# Sheet1.net
KiCad netlist of a schematic drawn in Altium Designer
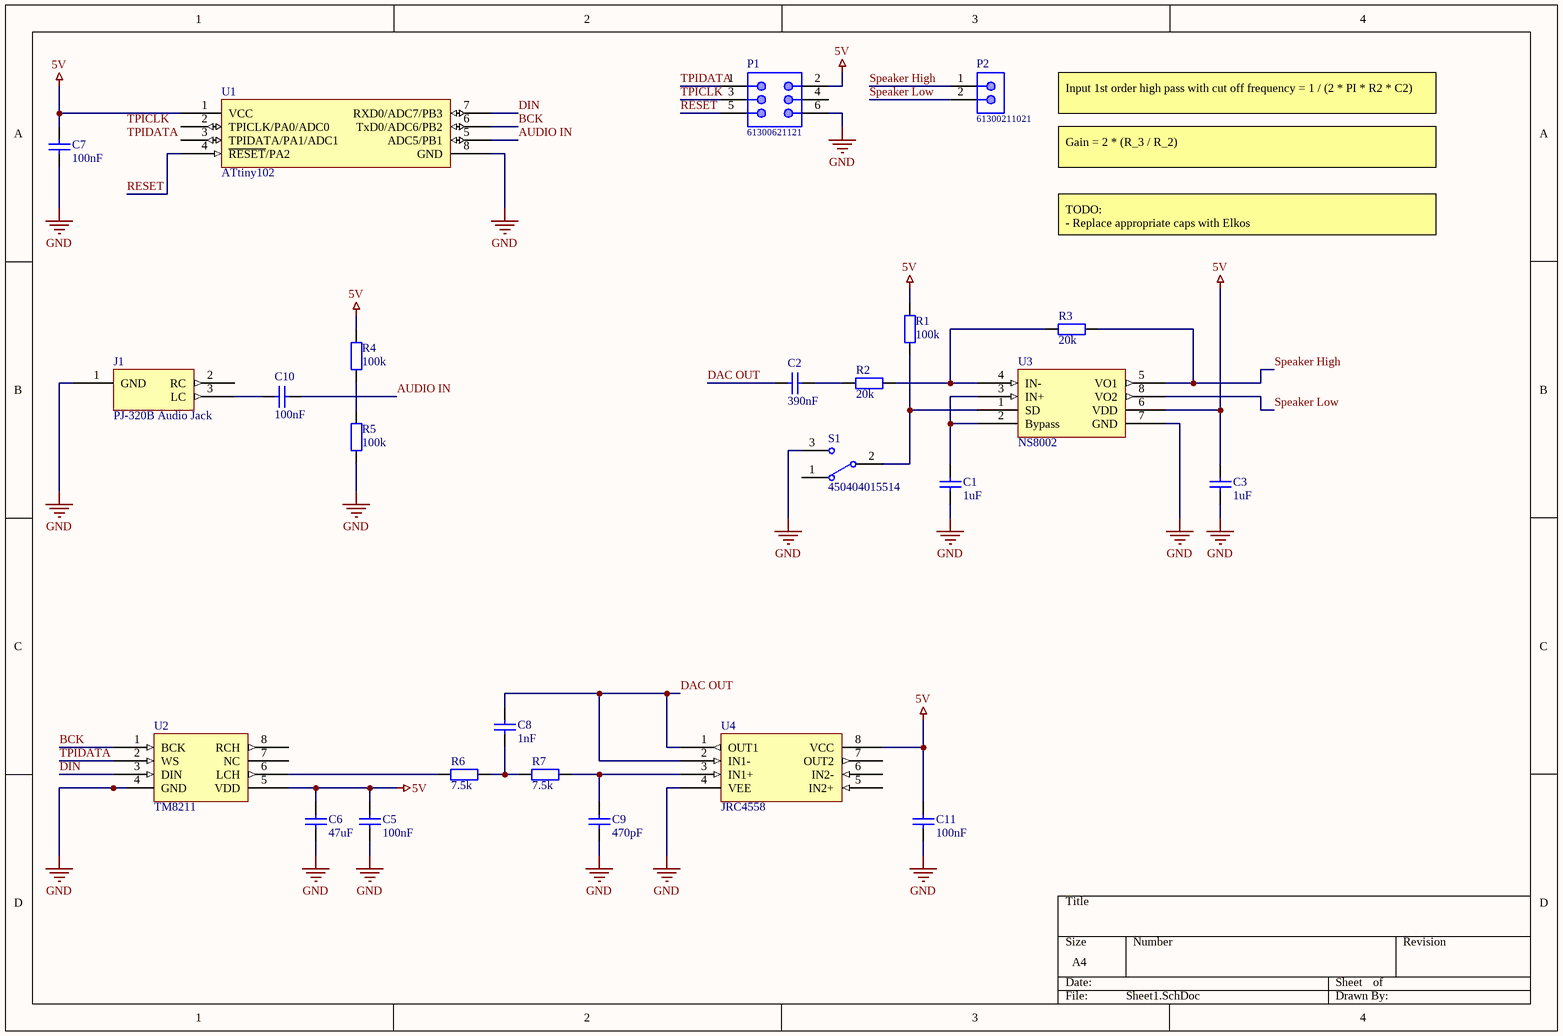
[diagram p0: Sheet1.SchDoc]

(export (version "E")
  (design (tool "Eeschema 10.0.6"))
  (components
    (comp (ref "C1")
      (value "1uF")
      (footprint "WCAP-CSGP_0805_H=1.25mm")
      (description "WCAP-CSGP General Purpose Ceramic Capacitors, size 0805, 1uF, +/-10%, 10VDC")
      (fields (field (name "PART NUMBER") "885012207022") (field (name "PUBLISHER") "Wurth Elektronik"))
      (libsource (lib "Altium_WCAP-CSGP (rev19a)") (part "885012207022"))
    )
    (comp (ref "C2")
      (value "390nF")
      (footprint "WCAP-CSGP_0402")
      (description "WCAP-CSGP General Purpose Ceramic Capacitors, size 0402, 1nF, +/-10%, 16VDC")
      (fields (field (name "PART NUMBER") "885012205025") (field (name "PUBLISHER") "Wurth Elektronik"))
      (libsource (lib "Altium_WCAP-CSGP (rev19a)") (part "885012205025"))
    )
    (comp (ref "C3")
      (value "1uF")
      (footprint "WCAP-CSGP_0805_H=1.25mm")
      (description "WCAP-CSGP General Purpose Ceramic Capacitors, size 0805, 1uF, +/-10%, 10VDC")
      (fields (field (name "PART NUMBER") "885012207022") (field (name "PUBLISHER") "Wurth Elektronik"))
      (libsource (lib "Altium_WCAP-CSGP (rev19a)") (part "885012207022"))
    )
    (comp (ref "C5")
      (value "100nF")
      (footprint "WCAP-CSGP_0805_H=1.25mm")
      (description "WCAP-CSGP General Purpose Ceramic Capacitors, size 0805, 1uF, +/-10%, 10VDC")
      (fields (field (name "PART NUMBER") "885012207022") (field (name "PUBLISHER") "Wurth Elektronik"))
      (libsource (lib "Altium_WCAP-CSGP (rev19a)") (part "885012207022"))
    )
    (comp (ref "C6")
      (value "47uF")
      (footprint "WCAP-CSGP_0805_H=1.25mm")
      (description "WCAP-CSGP General Purpose Ceramic Capacitors, size 0805, 1uF, +/-10%, 10VDC")
      (fields (field (name "PART NUMBER") "885012207022") (field (name "PUBLISHER") "Wurth Elektronik"))
      (libsource (lib "Altium_WCAP-CSGP (rev19a)") (part "885012207022"))
    )
    (comp (ref "C7")
      (value "100nF")
      (footprint "WCAP-CSGP_0805_H=1.25mm")
      (description "WCAP-CSGP General Purpose Ceramic Capacitors, size 0805, 1uF, +/-10%, 10VDC")
      (fields (field (name "PART NUMBER") "885012207022") (field (name "PUBLISHER") "Wurth Elektronik"))
      (libsource (lib "Altium_WCAP-CSGP (rev19a)") (part "885012207022"))
    )
    (comp (ref "C8")
      (value "1nF")
      (footprint "WCAP-CSGP_0402")
      (description "WCAP-CSGP General Purpose Ceramic Capacitors, size 0402, 1nF, +/-10%, 16VDC")
      (fields (field (name "PART NUMBER") "885012205025") (field (name "PUBLISHER") "Wurth Elektronik"))
      (libsource (lib "Altium_WCAP-CSGP (rev19a)") (part "885012205025"))
    )
    (comp (ref "C9")
      (value "470pF")
      (footprint "WCAP-CSGP_0402")
      (description "WCAP-CSGP General Purpose Ceramic Capacitors, size 0402, 1nF, +/-10%, 16VDC")
      (fields (field (name "PART NUMBER") "885012205025") (field (name "PUBLISHER") "Wurth Elektronik"))
      (libsource (lib "Altium_WCAP-CSGP (rev19a)") (part "885012205025"))
    )
    (comp (ref "C10")
      (value "100nF")
      (footprint "WCAP-CSGP_0805_H=1.25mm")
      (description "WCAP-CSGP General Purpose Ceramic Capacitors, size 0805, 1uF, +/-10%, 10VDC")
      (fields (field (name "PART NUMBER") "885012207022") (field (name "PUBLISHER") "Wurth Elektronik"))
      (libsource (lib "Altium_WCAP-CSGP (rev19a)") (part "885012207022"))
    )
    (comp (ref "C11")
      (value "100nF")
      (footprint "WCAP-CSGP_0805_H=1.25mm")
      (description "WCAP-CSGP General Purpose Ceramic Capacitors, size 0805, 1uF, +/-10%, 10VDC")
      (fields (field (name "PART NUMBER") "885012207022") (field (name "PUBLISHER") "Wurth Elektronik"))
      (libsource (lib "Altium_WCAP-CSGP (rev19a)") (part "885012207022"))
    )
    (comp (ref "J1")
      (value "PJ-320B Audio Jack")
      (footprint "PJ-320B Audio Jack")
      (libsource (lib "PJ-320B_AudioJack") (part "PJ-320B Audio Jack"))
    )
    (comp (ref "P1")
      (value "61300621121")
      (footprint "61300621121")
      (description "WR-PHD Pin Header, THT, pitch 2.54mm, Dual Row, Vertical, 6p")
      (fields (field (name "MANUFACTURER") "Wurth Elektronik"))
      (libsource (lib "61300311021_Altium_WR-PHD_rev20a") (part "61300621121"))
    )
    (comp (ref "P2")
      (value "61300211021")
      (footprint "61300211021")
      (description "WR-PHD Pin Header, THT, pitch 2.54mm, Single Row, Angled, 2p")
      (fields (field (name "MANUFACTURER") "Wurth Elektronik"))
      (libsource (lib "61300311021_Altium_WR-PHD_rev20a") (part "61300211021"))
    )
    (comp (ref "R1")
      (value "100k")
      (footprint "WRIS-PSMB_0805_H=0.22mm")
      (description "WRIS-PSMB Metal Plate Resistors, size 0805, 10mOhm, +/-1%, 0.5W")
      (fields (field (name "PART NUMBER") "580060720008") (field (name "PUBLISHER") "Wurth Elektronik"))
      (libsource (lib "") (part "580060720008_2"))
    )
    (comp (ref "R2")
      (value "20k")
      (footprint "WRIS-PSMB_0805_H=0.22mm")
      (description "WRIS-PSMB Metal Plate Resistors, size 0805, 10mOhm, +/-1%, 0.5W")
      (fields (field (name "PART NUMBER") "580060720008") (field (name "PUBLISHER") "Wurth Elektronik"))
      (libsource (lib "Altium_WRIS-PSMB (rev19a)") (part "580060720008"))
    )
    (comp (ref "R3")
      (value "20k")
      (footprint "WRIS-PSMB_0805_H=0.22mm")
      (description "WRIS-PSMB Metal Plate Resistors, size 0805, 10mOhm, +/-1%, 0.5W")
      (fields (field (name "PART NUMBER") "580060720008") (field (name "PUBLISHER") "Wurth Elektronik"))
      (libsource (lib "Altium_WRIS-PSMB (rev19a)") (part "580060720008"))
    )
    (comp (ref "R4")
      (value "100k")
      (footprint "WRIS-PSMB_0805_H=0.22mm")
      (description "WRIS-PSMB Metal Plate Resistors, size 0805, 10mOhm, +/-1%, 0.5W")
      (fields (field (name "PART NUMBER") "580060720008") (field (name "PUBLISHER") "Wurth Elektronik"))
      (libsource (lib "") (part "580060720008_1"))
    )
    (comp (ref "R5")
      (value "100k")
      (footprint "WRIS-PSMB_0805_H=0.22mm")
      (description "WRIS-PSMB Metal Plate Resistors, size 0805, 10mOhm, +/-1%, 0.5W")
      (fields (field (name "PART NUMBER") "580060720008") (field (name "PUBLISHER") "Wurth Elektronik"))
      (libsource (lib "") (part "580060720008_1"))
    )
    (comp (ref "R6")
      (value "7.5k")
      (footprint "WRIS-PSMB_0805_H=0.22mm")
      (description "WRIS-PSMB Metal Plate Resistors, size 0805, 10mOhm, +/-1%, 0.5W")
      (fields (field (name "PART NUMBER") "580060720008") (field (name "PUBLISHER") "Wurth Elektronik"))
      (libsource (lib "") (part "580060720008_3"))
    )
    (comp (ref "R7")
      (value "7.5k")
      (footprint "WRIS-PSMB_0805_H=0.22mm")
      (description "WRIS-PSMB Metal Plate Resistors, size 0805, 10mOhm, +/-1%, 0.5W")
      (fields (field (name "PART NUMBER") "580060720008") (field (name "PUBLISHER") "Wurth Elektronik"))
      (libsource (lib "") (part "580060720008_3"))
    )
    (comp (ref "S1")
      (value "450404015514")
      (footprint "450404015514")
      (description "WS-SLSU Mini SMT Slide Switch, Same Side Connection, Right Angled, SPDT")
      (fields (field (name "PUBLISHER") "Wurth Elektronik"))
      (libsource (lib "Altium_WS-SLSU (rev19b)") (part "450404015514"))
    )
    (comp (ref "U1")
      (value "ATtiny102")
      (footprint "ATtiny102")
      (libsource (lib "ATtiny102") (part "ATtiny102"))
    )
    (comp (ref "U2") (value "TM8211") (footprint "TM8211") (libsource (lib "TM8211") (part "TM8211")))
    (comp (ref "U3") (value "NS8002") (footprint "NS8002") (libsource (lib "NS8002") (part "NS8002")))
    (comp (ref "U4") (value "JRC4558") (footprint "JRC4558") (libsource (lib "JRC4558") (part "JRC4558")))
  )
  (nets
    (net (code "1") (name "/AUDIO IN") (class "Default")
      (node (ref "C10") (pin "2") (pinfunction "2_2") (pintype "passive"))
      (node (ref "U1") (pin "5") (pinfunction "ADC5/PB1_5") (pintype "bidirectional"))
    )
    (net (code "2") (name "/BCK") (class "Default")
      (node (ref "U1") (pin "6") (pinfunction "TxD0/ADC6/PB2_6") (pintype "bidirectional"))
      (node (ref "U2") (pin "1") (pinfunction "BCK_1") (pintype "input"))
    )
    (net (code "3") (name "/DAC OUT") (class "Default")
      (node (ref "C2") (pin "2") (pinfunction "2_2") (pintype "passive"))
      (node (ref "C8") (pin "2") (pinfunction "2_2") (pintype "passive"))
      (node (ref "U4") (pin "1") (pinfunction "OUT1_1") (pintype "output"))
      (node (ref "U4") (pin "2") (pinfunction "IN1-_2") (pintype "input"))
    )
    (net (code "4") (name "/DIN") (class "Default")
      (node (ref "U1") (pin "7") (pinfunction "RXD0/ADC7/PB3_7") (pintype "bidirectional"))
      (node (ref "U2") (pin "3") (pinfunction "DIN_3") (pintype "input"))
    )
    (net (code "5") (name "/RESET") (class "Default")
      (node (ref "P1") (pin "5") (pinfunction "5_5") (pintype "passive"))
      (node (ref "U1") (pin "4") (pinfunction "~{RESET}/PA2_4") (pintype "input"))
    )
    (net (code "6") (name "/Speaker High") (class "Default")
      (node (ref "P2") (pin "1") (pinfunction "1_1") (pintype "passive"))
      (node (ref "R3") (pin "1") (pinfunction "1_1") (pintype "passive"))
      (node (ref "U3") (pin "5") (pinfunction "VO1_5") (pintype "output"))
    )
    (net (code "7") (name "/Speaker Low") (class "Default")
      (node (ref "P2") (pin "2") (pinfunction "2_2") (pintype "passive"))
      (node (ref "U3") (pin "8") (pinfunction "VO2_8") (pintype "output"))
    )
    (net (code "8") (name "/TPICLK") (class "Default")
      (node (ref "P1") (pin "3") (pinfunction "3_3") (pintype "passive"))
    )
    (net (code "9") (name "/TPIDATA") (class "Default")
      (node (ref "P1") (pin "1") (pinfunction "1_1") (pintype "passive"))
      (node (ref "U2") (pin "2") (pinfunction "WS_2") (pintype "input"))
    )
    (net (code "10") (name "5V") (class "Default")
      (node (ref "C11") (pin "1") (pinfunction "1_1") (pintype "passive"))
      (node (ref "C3") (pin "1") (pinfunction "1_1") (pintype "passive"))
      (node (ref "C5") (pin "1") (pinfunction "1_1") (pintype "passive"))
      (node (ref "C6") (pin "1") (pinfunction "1_1") (pintype "passive"))
      (node (ref "C7") (pin "1") (pinfunction "1_1") (pintype "passive"))
      (node (ref "P1") (pin "2") (pinfunction "2_2") (pintype "passive"))
      (node (ref "R1") (pin "2") (pinfunction "2_2") (pintype "passive"))
      (node (ref "R4") (pin "1") (pinfunction "1_1") (pintype "passive"))
      (node (ref "U1") (pin "1") (pinfunction "VCC_1") (pintype "power_in"))
      (node (ref "U2") (pin "5") (pinfunction "VDD_5") (pintype "power_in"))
      (node (ref "U3") (pin "6") (pinfunction "VDD_6") (pintype "power_in"))
      (node (ref "U4") (pin "8") (pinfunction "VCC_8") (pintype "power_in"))
    )
    (net (code "11") (name "GND") (class "Default")
      (node (ref "C1") (pin "1") (pinfunction "1_1") (pintype "passive"))
      (node (ref "C11") (pin "2") (pinfunction "2_2") (pintype "passive"))
      (node (ref "C3") (pin "2") (pinfunction "2_2") (pintype "passive"))
      (node (ref "C5") (pin "2") (pinfunction "2_2") (pintype "passive"))
      (node (ref "C6") (pin "2") (pinfunction "2_2") (pintype "passive"))
      (node (ref "C7") (pin "2") (pinfunction "2_2") (pintype "passive"))
      (node (ref "C9") (pin "1") (pinfunction "1_1") (pintype "passive"))
      (node (ref "J1") (pin "1") (pinfunction "GND_1") (pintype "passive"))
      (node (ref "P1") (pin "6") (pinfunction "6_6") (pintype "passive"))
      (node (ref "R5") (pin "2") (pinfunction "2_2") (pintype "passive"))
      (node (ref "S1") (pin "3") (pinfunction "3_3") (pintype "passive"))
      (node (ref "U1") (pin "8") (pinfunction "GND_8") (pintype "passive"))
      (node (ref "U2") (pin "4") (pinfunction "GND_4") (pintype "passive"))
      (node (ref "U3") (pin "7") (pinfunction "GND_7") (pintype "passive"))
      (node (ref "U4") (pin "4") (pinfunction "VEE_4") (pintype "passive"))
    )
    (net (code "12") (name "Net-(C2-Pad1)") (class "Default")
      (node (ref "C2") (pin "1") (pinfunction "1_1") (pintype "passive"))
      (node (ref "R2") (pin "2") (pinfunction "2_2") (pintype "passive"))
    )
    (net (code "13") (name "Net-(C8-Pad1)") (class "Default")
      (node (ref "C8") (pin "1") (pinfunction "1_1") (pintype "passive"))
      (node (ref "R6") (pin "2") (pinfunction "2_2") (pintype "passive"))
      (node (ref "R7") (pin "1") (pinfunction "1_1") (pintype "passive"))
    )
    (net (code "14") (name "Net-(J1-LC)") (class "Default")
      (node (ref "C10") (pin "1") (pinfunction "1_1") (pintype "passive"))
      (node (ref "J1") (pin "3") (pinfunction "LC_3") (pintype "output"))
    )
    (net (code "15") (name "Net-(R4-Pad2)") (class "Default")
      (node (ref "R4") (pin "2") (pinfunction "2_2") (pintype "passive"))
      (node (ref "R5") (pin "1") (pinfunction "1_1") (pintype "passive"))
    )
    (net (code "16") (name "Net-(S1-COM)") (class "Default")
      (node (ref "R1") (pin "1") (pinfunction "1_1") (pintype "passive"))
      (node (ref "S1") (pin "2") (pinfunction "COM_2") (pintype "passive"))
      (node (ref "U3") (pin "1") (pinfunction "SD_1") (pintype "passive"))
    )
    (net (code "17") (name "Net-(U2-LCH)") (class "Default")
      (node (ref "R6") (pin "1") (pinfunction "1_1") (pintype "passive"))
      (node (ref "U2") (pin "6") (pinfunction "LCH_6") (pintype "output"))
    )
    (net (code "18") (name "Net-(U3-Bypass)") (class "Default")
      (node (ref "C1") (pin "2") (pinfunction "2_2") (pintype "passive"))
      (node (ref "U3") (pin "2") (pinfunction "Bypass_2") (pintype "passive"))
      (node (ref "U3") (pin "3") (pinfunction "IN+_3") (pintype "input"))
    )
    (net (code "19") (name "Net-(U3-IN-)") (class "Default")
      (node (ref "R2") (pin "1") (pinfunction "1_1") (pintype "passive"))
      (node (ref "R3") (pin "2") (pinfunction "2_2") (pintype "passive"))
      (node (ref "U3") (pin "4") (pinfunction "IN-_4") (pintype "input"))
    )
    (net (code "20") (name "Net-(U4-IN1+)") (class "Default")
      (node (ref "C9") (pin "2") (pinfunction "2_2") (pintype "passive"))
      (node (ref "R7") (pin "2") (pinfunction "2_2") (pintype "passive"))
      (node (ref "U4") (pin "3") (pinfunction "IN1+_3") (pintype "input"))
    )
    (net (code "21") (name "unconnected-(J1-RC-Pad2)") (class "Default")
      (node (ref "J1") (pin "2") (pinfunction "RC_2") (pintype "output"))
    )
    (net (code "22") (name "unconnected-(P1-Pad4)") (class "Default")
      (node (ref "P1") (pin "4") (pinfunction "4_4") (pintype "passive"))
    )
    (net (code "23") (name "unconnected-(S1-Pad1)") (class "Default")
      (node (ref "S1") (pin "1") (pinfunction "1_1") (pintype "passive"))
    )
    (net (code "24") (name "unconnected-(U1-TPICLK{slash}PA0{slash}ADC0-Pad2)") (class "Default")
      (node (ref "U1") (pin "2") (pinfunction "TPICLK/PA0/ADC0_2") (pintype "bidirectional"))
    )
    (net (code "25") (name "unconnected-(U1-TPIDATA{slash}PA1{slash}ADC1-Pad3)") (class "Default")
      (node (ref "U1") (pin "3") (pinfunction "TPIDATA/PA1/ADC1_3") (pintype "bidirectional"))
    )
    (net (code "26") (name "unconnected-(U2-NC-Pad7)") (class "Default")
      (node (ref "U2") (pin "7") (pinfunction "NC_7") (pintype "open_collector"))
    )
    (net (code "27") (name "unconnected-(U2-RCH-Pad8)") (class "Default")
      (node (ref "U2") (pin "8") (pinfunction "RCH_8") (pintype "output"))
    )
    (net (code "28") (name "unconnected-(U4-IN2+-Pad5)") (class "Default")
      (node (ref "U4") (pin "5") (pinfunction "IN2+_5") (pintype "input"))
    )
    (net (code "29") (name "unconnected-(U4-IN2--Pad6)") (class "Default")
      (node (ref "U4") (pin "6") (pinfunction "IN2-_6") (pintype "input"))
    )
    (net (code "30") (name "unconnected-(U4-OUT2-Pad7)") (class "Default")
      (node (ref "U4") (pin "7") (pinfunction "OUT2_7") (pintype "output"))
    )
  )
)
